# HDMI_SWITCH.net
KiCad netlist of a schematic drawn in Altium Designer
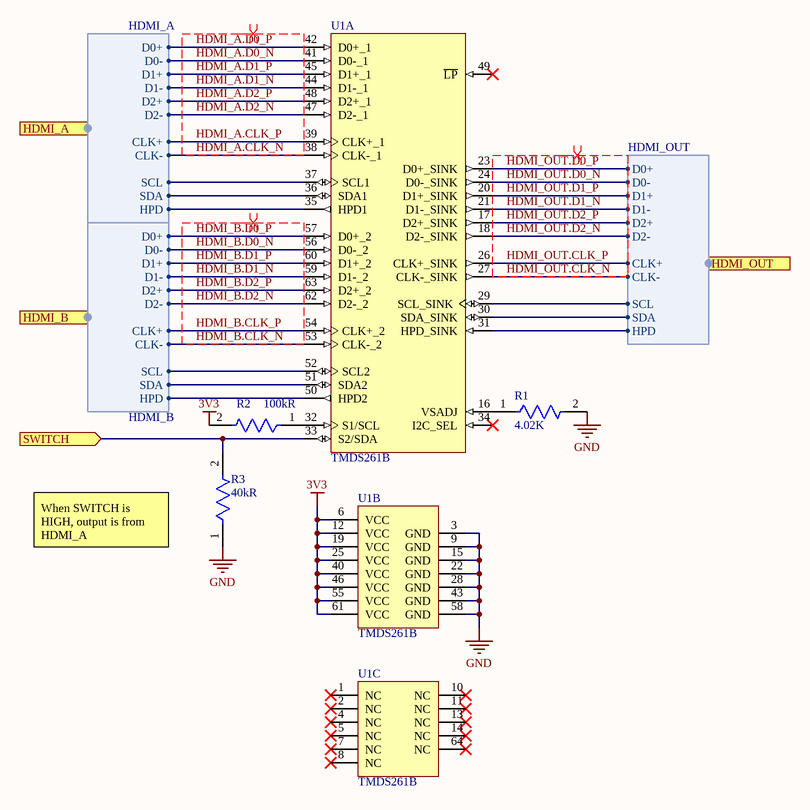
[diagram p0: HDMI_SWITCH.SchDoc]

(export (version "E")
  (design (tool "Eeschema 10.0.6"))
  (components
    (comp (ref "R1")
      (value "4.02K")
      (footprint "FP-RT0402-MFG")
      (description "RT0402 4.02KΩ 0.063W 50 ppm/°C 1.00%")
      (fields (field (name "Comment") "RT0402"))
      (libsource (lib "KVM Library") (part "RT0402"))
    )
    (comp (ref "R2")
      (value "RK73H1JLTD1003F")
      (footprint "FP-RK73H1J-IPC_C")
      (description "100kΩ ±1% 0.1W Chip Resistor 0603 Thick Film AEC-Q200 Qualified")
      (fields (field (name "TOLERANCE") "1%") (field (name "RESISTANCE") "100kR"))
      (libsource (lib "Altium Content Vault") (part "1029c3af85768c4190bb7ad29bc67b5"))
    )
    (comp (ref "R3")
      (value "CRCW080540K0FKEA")
      (footprint "FP-CRCW0805-e3-MFG")
      (description "RES Thick Film, 40kΩ, 1%, 0.125W, 100ppm/°C, 0805")
      (fields (field (name "TOLERANCE") "1%") (field (name "RESISTANCE") "40kR"))
      (libsource (lib "Altium Content Vault") (part "1029c3af85768c4190bb7ad29bc67b5"))
    )
    (comp (ref "U1")
      (value "TMDS261B")
      (footprint "PAG0064A_N")
      (description "3-Gbps 2-to-1 HDMI/DVI mux with adaptive equalization 64-TQFP 0 to 70")
      (libsource (lib "KVM Library") (part "TMDS261B"))
    )
  )
  (nets
    (net (code "4") (name "/HDMI_A.CLK_N") (class "Default")
      (node (ref "U1") (pin "38") (pinfunction "CLK-_1_38") (pintype "input"))
    )
    (net (code "5") (name "/HDMI_A.CLK_P") (class "Default")
      (node (ref "U1") (pin "39") (pinfunction "CLK+_1_39") (pintype "input"))
    )
    (net (code "6") (name "/HDMI_A.D0_N") (class "Default")
      (node (ref "U1") (pin "41") (pinfunction "D0-_1_41") (pintype "input"))
    )
    (net (code "7") (name "/HDMI_A.D0_P") (class "Default")
      (node (ref "U1") (pin "42") (pinfunction "D0+_1_42") (pintype "input"))
    )
    (net (code "8") (name "/HDMI_A.D1_N") (class "Default")
      (node (ref "U1") (pin "44") (pinfunction "D1-_1_44") (pintype "input"))
    )
    (net (code "9") (name "/HDMI_A.D1_P") (class "Default")
      (node (ref "U1") (pin "45") (pinfunction "D1+_1_45") (pintype "input"))
    )
    (net (code "10") (name "/HDMI_A.D2_N") (class "Default")
      (node (ref "U1") (pin "47") (pinfunction "D2-_1_47") (pintype "input"))
    )
    (net (code "11") (name "/HDMI_A.D2_P") (class "Default")
      (node (ref "U1") (pin "48") (pinfunction "D2+_1_48") (pintype "input"))
    )
    (net (code "13") (name "/HDMI_B.CLK_N") (class "Default")
      (node (ref "U1") (pin "53") (pinfunction "CLK-_2_53") (pintype "input"))
    )
    (net (code "14") (name "/HDMI_B.CLK_P") (class "Default")
      (node (ref "U1") (pin "54") (pinfunction "CLK+_2_54") (pintype "input"))
    )
    (net (code "15") (name "/HDMI_B.D0_N") (class "Default")
      (node (ref "U1") (pin "56") (pinfunction "D0-_2_56") (pintype "input"))
    )
    (net (code "16") (name "/HDMI_B.D0_P") (class "Default")
      (node (ref "U1") (pin "57") (pinfunction "D0+_2_57") (pintype "input"))
    )
    (net (code "17") (name "/HDMI_B.D1_N") (class "Default")
      (node (ref "U1") (pin "59") (pinfunction "D1-_2_59") (pintype "input"))
    )
    (net (code "18") (name "/HDMI_B.D1_P") (class "Default")
      (node (ref "U1") (pin "60") (pinfunction "D1+_2_60") (pintype "input"))
    )
    (net (code "19") (name "/HDMI_B.D2_N") (class "Default")
      (node (ref "U1") (pin "62") (pinfunction "D2-_2_62") (pintype "input"))
    )
    (net (code "20") (name "/HDMI_B.D2_P") (class "Default")
      (node (ref "U1") (pin "63") (pinfunction "D2+_2_63") (pintype "input"))
    )
    (net (code "21") (name "/HDMI_OUT.CLK_N") (class "Default")
      (node (ref "U1") (pin "27") (pinfunction "CLK-_SINK_27") (pintype "output"))
    )
    (net (code "22") (name "/HDMI_OUT.CLK_P") (class "Default")
      (node (ref "U1") (pin "26") (pinfunction "CLK+_SINK_26") (pintype "output"))
    )
    (net (code "23") (name "/HDMI_OUT.D0_N") (class "Default")
      (node (ref "U1") (pin "24") (pinfunction "D0-_SINK_24") (pintype "output"))
    )
    (net (code "24") (name "/HDMI_OUT.D0_P") (class "Default")
      (node (ref "U1") (pin "23") (pinfunction "D0+_SINK_23") (pintype "output"))
    )
    (net (code "25") (name "/HDMI_OUT.D1_N") (class "Default")
      (node (ref "U1") (pin "21") (pinfunction "D1-_SINK_21") (pintype "output"))
    )
    (net (code "26") (name "/HDMI_OUT.D1_P") (class "Default")
      (node (ref "U1") (pin "20") (pinfunction "D1+_SINK_20") (pintype "output"))
    )
    (net (code "27") (name "/HDMI_OUT.D2_N") (class "Default")
      (node (ref "U1") (pin "18") (pinfunction "D2-_SINK_18") (pintype "output"))
    )
    (net (code "28") (name "/HDMI_OUT.D2_P") (class "Default")
      (node (ref "U1") (pin "17") (pinfunction "D2+_SINK_17") (pintype "output"))
    )
    (net (code "29") (name "/SWITCH") (class "Default")
      (node (ref "R3") (pin "2") (pinfunction "2_2") (pintype "passive"))
      (node (ref "U1") (pin "33") (pinfunction "S2/SDA_33") (pintype "bidirectional"))
    )
    (net (code "32") (name "3V3") (class "Default")
      (node (ref "R2") (pin "2") (pinfunction "2_2") (pintype "passive"))
      (node (ref "U1") (pin "12") (pinfunction "VCC_12") (pintype "power_in"))
      (node (ref "U1") (pin "19") (pinfunction "VCC_19") (pintype "power_in"))
      (node (ref "U1") (pin "25") (pinfunction "VCC_25") (pintype "power_in"))
      (node (ref "U1") (pin "40") (pinfunction "VCC_40") (pintype "power_in"))
      (node (ref "U1") (pin "46") (pinfunction "VCC_46") (pintype "power_in"))
      (node (ref "U1") (pin "55") (pinfunction "VCC_55") (pintype "power_in"))
      (node (ref "U1") (pin "6") (pinfunction "VCC_6") (pintype "power_in"))
      (node (ref "U1") (pin "61") (pinfunction "VCC_61") (pintype "power_in"))
    )
    (net (code "33") (name "GND") (class "Default")
      (node (ref "R1") (pin "2") (pinfunction "2_2") (pintype "passive"))
      (node (ref "R3") (pin "1") (pinfunction "1_1") (pintype "passive"))
      (node (ref "U1") (pin "15") (pinfunction "GND_15") (pintype "power_in"))
      (node (ref "U1") (pin "22") (pinfunction "GND_22") (pintype "power_in"))
      (node (ref "U1") (pin "28") (pinfunction "GND_28") (pintype "power_in"))
      (node (ref "U1") (pin "3") (pinfunction "GND_3") (pintype "power_in"))
      (node (ref "U1") (pin "43") (pinfunction "GND_43") (pintype "power_in"))
      (node (ref "U1") (pin "58") (pinfunction "GND_58") (pintype "power_in"))
      (node (ref "U1") (pin "9") (pinfunction "GND_9") (pintype "power_in"))
    )
    (net (code "34") (name "Net-(U1A-S1{slash}SCL)") (class "Default")
      (node (ref "R2") (pin "1") (pinfunction "1_1") (pintype "passive"))
      (node (ref "U1") (pin "32") (pinfunction "S1/SCL_32") (pintype "input"))
    )
    (net (code "35") (name "Net-(U1A-VSADJ)") (class "Default")
      (node (ref "R1") (pin "1") (pinfunction "1_1") (pintype "passive"))
      (node (ref "U1") (pin "16") (pinfunction "VSADJ_16") (pintype "input"))
    )
    (net (code "36") (name "unconnected-(U1A-HPD1-Pad35)") (class "Default")
      (node (ref "U1") (pin "35") (pinfunction "HPD1_35") (pintype "output"))
    )
    (net (code "37") (name "unconnected-(U1A-HPD2-Pad50)") (class "Default")
      (node (ref "U1") (pin "50") (pinfunction "HPD2_50") (pintype "output"))
    )
    (net (code "38") (name "unconnected-(U1A-HPD_SINK-Pad31)") (class "Default")
      (node (ref "U1") (pin "31") (pinfunction "HPD_SINK_31") (pintype "input"))
    )
    (net (code "39") (name "unconnected-(U1A-I2C_SEL-Pad34)") (class "Default")
      (node (ref "U1") (pin "34") (pinfunction "I2C_SEL_34") (pintype "input+no_connect"))
    )
    (net (code "40") (name "unconnected-(U1A-SCL1-Pad37)") (class "Default")
      (node (ref "U1") (pin "37") (pinfunction "SCL1_37") (pintype "bidirectional"))
    )
    (net (code "41") (name "unconnected-(U1A-SCL2-Pad52)") (class "Default")
      (node (ref "U1") (pin "52") (pinfunction "SCL2_52") (pintype "bidirectional"))
    )
    (net (code "42") (name "unconnected-(U1A-SCL_SINK-Pad29)") (class "Default")
      (node (ref "U1") (pin "29") (pinfunction "SCL_SINK_29") (pintype "bidirectional"))
    )
    (net (code "43") (name "unconnected-(U1A-SDA1-Pad36)") (class "Default")
      (node (ref "U1") (pin "36") (pinfunction "SDA1_36") (pintype "bidirectional"))
    )
    (net (code "44") (name "unconnected-(U1A-SDA2-Pad51)") (class "Default")
      (node (ref "U1") (pin "51") (pinfunction "SDA2_51") (pintype "bidirectional"))
    )
    (net (code "45") (name "unconnected-(U1A-SDA_SINK-Pad30)") (class "Default")
      (node (ref "U1") (pin "30") (pinfunction "SDA_SINK_30") (pintype "bidirectional"))
    )
    (net (code "46") (name "unconnected-(U1A-~{LP}-Pad49)") (class "Default")
      (node (ref "U1") (pin "49") (pinfunction "~{LP}_49") (pintype "input+no_connect"))
    )
    (net (code "47") (name "unconnected-(U1C-NC-Pad1)") (class "Default")
      (node (ref "U1") (pin "1") (pinfunction "NC_1") (pintype "passive+no_connect"))
    )
    (net (code "48") (name "unconnected-(U1C-NC-Pad2)") (class "Default")
      (node (ref "U1") (pin "2") (pinfunction "NC_2") (pintype "passive+no_connect"))
    )
    (net (code "49") (name "unconnected-(U1C-NC-Pad4)") (class "Default")
      (node (ref "U1") (pin "4") (pinfunction "NC_4") (pintype "passive+no_connect"))
    )
    (net (code "50") (name "unconnected-(U1C-NC-Pad5)") (class "Default")
      (node (ref "U1") (pin "5") (pinfunction "NC_5") (pintype "passive+no_connect"))
    )
    (net (code "51") (name "unconnected-(U1C-NC-Pad7)") (class "Default")
      (node (ref "U1") (pin "7") (pinfunction "NC_7") (pintype "passive+no_connect"))
    )
    (net (code "52") (name "unconnected-(U1C-NC-Pad8)") (class "Default")
      (node (ref "U1") (pin "8") (pinfunction "NC_8") (pintype "passive+no_connect"))
    )
    (net (code "53") (name "unconnected-(U1C-NC-Pad10)") (class "Default")
      (node (ref "U1") (pin "10") (pinfunction "NC_10") (pintype "passive+no_connect"))
    )
    (net (code "54") (name "unconnected-(U1C-NC-Pad11)") (class "Default")
      (node (ref "U1") (pin "11") (pinfunction "NC_11") (pintype "passive+no_connect"))
    )
    (net (code "55") (name "unconnected-(U1C-NC-Pad13)") (class "Default")
      (node (ref "U1") (pin "13") (pinfunction "NC_13") (pintype "passive+no_connect"))
    )
    (net (code "56") (name "unconnected-(U1C-NC-Pad14)") (class "Default")
      (node (ref "U1") (pin "14") (pinfunction "NC_14") (pintype "passive+no_connect"))
    )
    (net (code "57") (name "unconnected-(U1C-NC-Pad64)") (class "Default")
      (node (ref "U1") (pin "64") (pinfunction "NC_64") (pintype "passive+no_connect"))
    )
  )
)
